# main.net
KiCad netlist of a schematic drawn in EAGLE
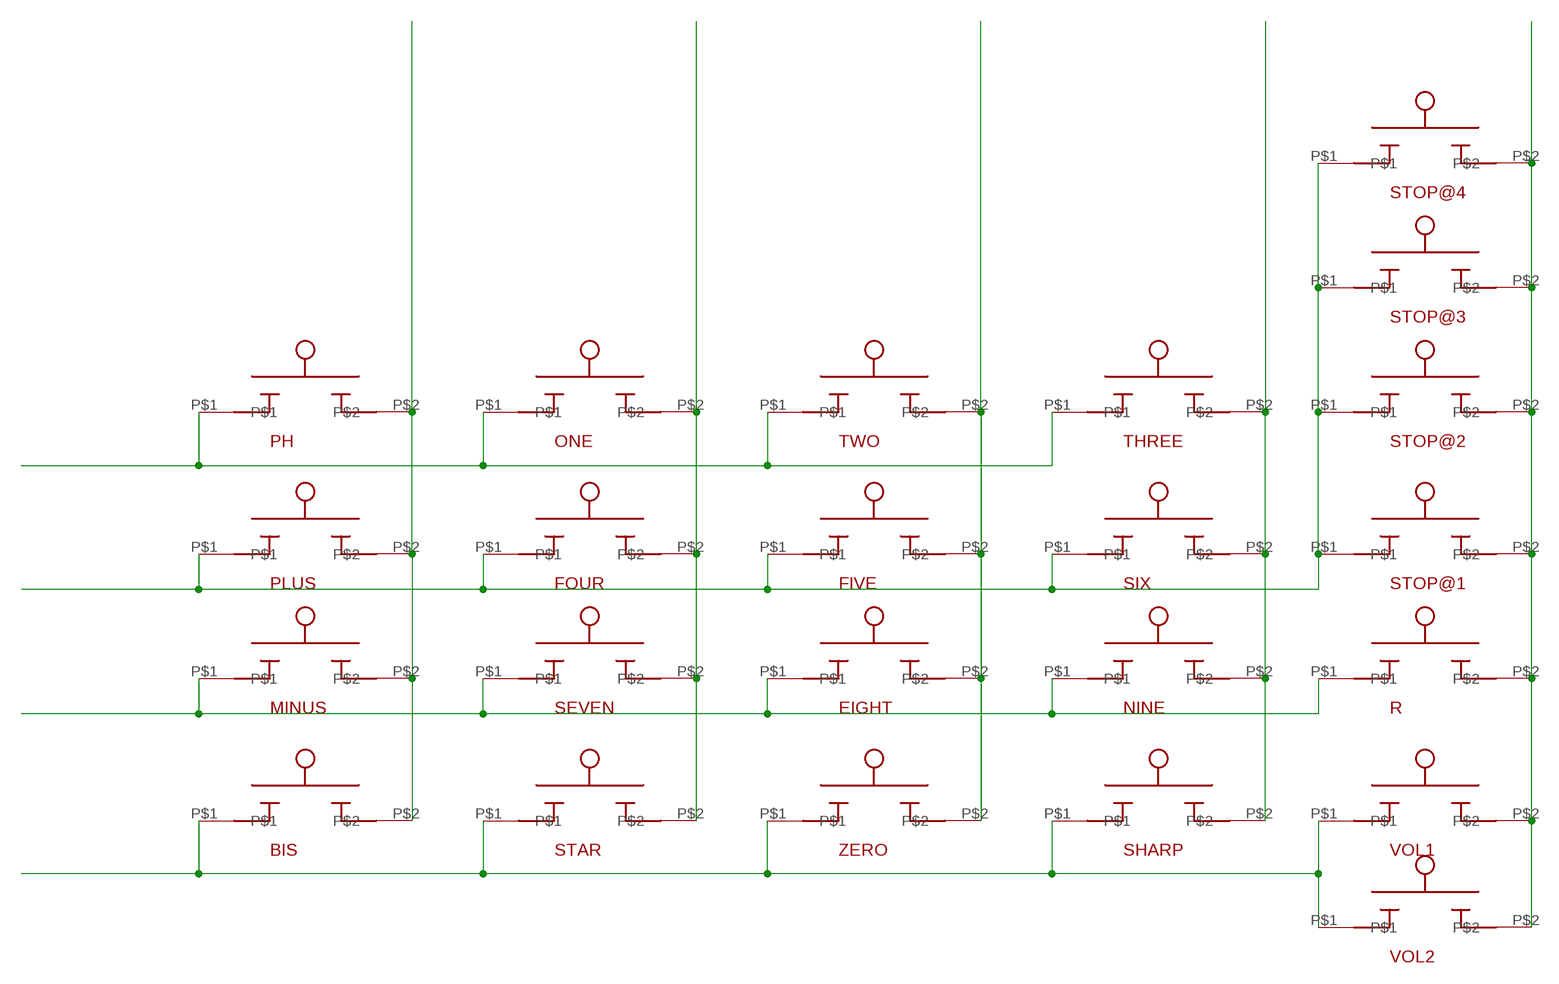
[diagram p0: schematic, sheet 1]

(export (version "E")
  (design (tool "Eeschema 10.0.6"))
  (components
    (comp (ref "BIS")
      (value "MEMBRANE_BUTTON")
      (footprint "eagle-import:MEMBRANE_BUTTON")
      (libsource (lib "eagle-import") (part "7_segment_lib_1964360_MEMBRANE_BUTTON"))
    )
    (comp (ref "EIGHT")
      (value "MEMBRANE_BUTTON")
      (footprint "eagle-import:MEMBRANE_BUTTON")
      (libsource (lib "eagle-import") (part "MEMBRANE_BUTTON"))
    )
    (comp (ref "FIVE")
      (value "MEMBRANE_BUTTON")
      (footprint "eagle-import:MEMBRANE_BUTTON")
      (libsource (lib "eagle-import") (part "MEMBRANE_BUTTON"))
    )
    (comp (ref "FOUR")
      (value "MEMBRANE_BUTTON")
      (footprint "eagle-import:MEMBRANE_BUTTON")
      (libsource (lib "eagle-import") (part "MEMBRANE_BUTTON"))
    )
    (comp (ref "MINUS")
      (value "MEMBRANE_BUTTON")
      (footprint "eagle-import:MEMBRANE_BUTTON")
      (libsource (lib "eagle-import") (part "MEMBRANE_BUTTON"))
    )
    (comp (ref "NINE")
      (value "MEMBRANE_BUTTON")
      (footprint "eagle-import:MEMBRANE_BUTTON")
      (libsource (lib "eagle-import") (part "MEMBRANE_BUTTON"))
    )
    (comp (ref "ONE")
      (value "MEMBRANE_BUTTON")
      (footprint "eagle-import:MEMBRANE_BUTTON")
      (libsource (lib "eagle-import") (part "MEMBRANE_BUTTON"))
    )
    (comp (ref "PH")
      (value "MEMBRANE_BUTTON")
      (footprint "eagle-import:MEMBRANE_BUTTON")
      (libsource (lib "eagle-import") (part "MEMBRANE_BUTTON"))
    )
    (comp (ref "PLUS")
      (value "MEMBRANE_BUTTON")
      (footprint "eagle-import:MEMBRANE_BUTTON")
      (libsource (lib "eagle-import") (part "MEMBRANE_BUTTON"))
    )
    (comp (ref "R")
      (value "MEMBRANE_BUTTON")
      (footprint "eagle-import:MEMBRANE_BUTTON")
      (libsource (lib "eagle-import") (part "MEMBRANE_BUTTON"))
    )
    (comp (ref "SEVEN")
      (value "MEMBRANE_BUTTON")
      (footprint "eagle-import:MEMBRANE_BUTTON")
      (libsource (lib "eagle-import") (part "MEMBRANE_BUTTON"))
    )
    (comp (ref "SHARP")
      (value "MEMBRANE_BUTTON")
      (footprint "eagle-import:MEMBRANE_BUTTON")
      (libsource (lib "eagle-import") (part "MEMBRANE_BUTTON"))
    )
    (comp (ref "SIX")
      (value "MEMBRANE_BUTTON")
      (footprint "eagle-import:MEMBRANE_BUTTON")
      (libsource (lib "eagle-import") (part "MEMBRANE_BUTTON"))
    )
    (comp (ref "STAR")
      (value "MEMBRANE_BUTTON")
      (footprint "eagle-import:MEMBRANE_BUTTON")
      (libsource (lib "eagle-import") (part "MEMBRANE_BUTTON"))
    )
    (comp (ref "STOP@1")
      (value "MEMBRANE_BUTTON")
      (footprint "eagle-import:MEMBRANE_BUTTON")
      (libsource (lib "eagle-import") (part "MEMBRANE_BUTTON"))
    )
    (comp (ref "STOP@2")
      (value "MEMBRANE_BUTTON")
      (footprint "eagle-import:MEMBRANE_BUTTON")
      (libsource (lib "eagle-import") (part "MEMBRANE_BUTTON"))
    )
    (comp (ref "STOP@3")
      (value "MEMBRANE_BUTTON")
      (footprint "eagle-import:MEMBRANE_BUTTON")
      (libsource (lib "eagle-import") (part "MEMBRANE_BUTTON"))
    )
    (comp (ref "STOP@4")
      (value "MEMBRANE_BUTTON")
      (footprint "eagle-import:MEMBRANE_BUTTON")
      (libsource (lib "eagle-import") (part "MEMBRANE_BUTTON"))
    )
    (comp (ref "THREE")
      (value "MEMBRANE_BUTTON")
      (footprint "eagle-import:MEMBRANE_BUTTON")
      (libsource (lib "eagle-import") (part "MEMBRANE_BUTTON"))
    )
    (comp (ref "TWO")
      (value "MEMBRANE_BUTTON")
      (footprint "eagle-import:MEMBRANE_BUTTON")
      (libsource (lib "eagle-import") (part "MEMBRANE_BUTTON"))
    )
    (comp (ref "VOL1")
      (value "MEMBRANE_BUTTON")
      (footprint "eagle-import:MEMBRANE_BUTTON")
      (libsource (lib "eagle-import") (part "MEMBRANE_BUTTON"))
    )
    (comp (ref "VOL2")
      (value "MEMBRANE_BUTTON")
      (footprint "eagle-import:MEMBRANE_BUTTON")
      (libsource (lib "eagle-import") (part "MEMBRANE_BUTTON"))
    )
    (comp (ref "ZERO")
      (value "MEMBRANE_BUTTON")
      (footprint "eagle-import:MEMBRANE_BUTTON")
      (libsource (lib "eagle-import") (part "MEMBRANE_BUTTON"))
    )
  )
  (nets
    (net (code "1") (name "Net-(BIS-PadP$1)") (class "Default")
      (node (ref "BIS") (pin "P$1") (pinfunction "P$1_P$1") (pintype "bidirectional"))
      (node (ref "SHARP") (pin "P$1") (pinfunction "P$1_P$1") (pintype "bidirectional"))
      (node (ref "STAR") (pin "P$1") (pinfunction "P$1_P$1") (pintype "bidirectional"))
      (node (ref "VOL1") (pin "P$1") (pinfunction "P$1_P$1") (pintype "bidirectional"))
      (node (ref "VOL2") (pin "P$1") (pinfunction "P$1_P$1") (pintype "bidirectional"))
      (node (ref "ZERO") (pin "P$1") (pinfunction "P$1_P$1") (pintype "bidirectional"))
    )
    (net (code "2") (name "Net-(BIS-PadP$2)") (class "Default")
      (node (ref "BIS") (pin "P$2") (pinfunction "P$2_P$2") (pintype "bidirectional"))
      (node (ref "MINUS") (pin "P$2") (pinfunction "P$2_P$2") (pintype "bidirectional"))
      (node (ref "PH") (pin "P$2") (pinfunction "P$2_P$2") (pintype "bidirectional"))
      (node (ref "PLUS") (pin "P$2") (pinfunction "P$2_P$2") (pintype "bidirectional"))
    )
    (net (code "3") (name "Net-(EIGHT-PadP$1)") (class "Default")
      (node (ref "EIGHT") (pin "P$1") (pinfunction "P$1_P$1") (pintype "bidirectional"))
      (node (ref "MINUS") (pin "P$1") (pinfunction "P$1_P$1") (pintype "bidirectional"))
      (node (ref "NINE") (pin "P$1") (pinfunction "P$1_P$1") (pintype "bidirectional"))
      (node (ref "R") (pin "P$1") (pinfunction "P$1_P$1") (pintype "bidirectional"))
      (node (ref "SEVEN") (pin "P$1") (pinfunction "P$1_P$1") (pintype "bidirectional"))
    )
    (net (code "4") (name "Net-(EIGHT-PadP$2)") (class "Default")
      (node (ref "EIGHT") (pin "P$2") (pinfunction "P$2_P$2") (pintype "bidirectional"))
      (node (ref "FIVE") (pin "P$2") (pinfunction "P$2_P$2") (pintype "bidirectional"))
      (node (ref "TWO") (pin "P$2") (pinfunction "P$2_P$2") (pintype "bidirectional"))
      (node (ref "ZERO") (pin "P$2") (pinfunction "P$2_P$2") (pintype "bidirectional"))
    )
    (net (code "5") (name "Net-(FIVE-PadP$1)") (class "Default")
      (node (ref "FIVE") (pin "P$1") (pinfunction "P$1_P$1") (pintype "bidirectional"))
      (node (ref "FOUR") (pin "P$1") (pinfunction "P$1_P$1") (pintype "bidirectional"))
      (node (ref "PLUS") (pin "P$1") (pinfunction "P$1_P$1") (pintype "bidirectional"))
      (node (ref "SIX") (pin "P$1") (pinfunction "P$1_P$1") (pintype "bidirectional"))
      (node (ref "STOP@1") (pin "P$1") (pinfunction "P$1_P$1") (pintype "bidirectional"))
      (node (ref "STOP@2") (pin "P$1") (pinfunction "P$1_P$1") (pintype "bidirectional"))
      (node (ref "STOP@3") (pin "P$1") (pinfunction "P$1_P$1") (pintype "bidirectional"))
      (node (ref "STOP@4") (pin "P$1") (pinfunction "P$1_P$1") (pintype "bidirectional"))
    )
    (net (code "6") (name "Net-(FOUR-PadP$2)") (class "Default")
      (node (ref "FOUR") (pin "P$2") (pinfunction "P$2_P$2") (pintype "bidirectional"))
      (node (ref "ONE") (pin "P$2") (pinfunction "P$2_P$2") (pintype "bidirectional"))
      (node (ref "SEVEN") (pin "P$2") (pinfunction "P$2_P$2") (pintype "bidirectional"))
      (node (ref "STAR") (pin "P$2") (pinfunction "P$2_P$2") (pintype "bidirectional"))
    )
    (net (code "7") (name "Net-(NINE-PadP$2)") (class "Default")
      (node (ref "NINE") (pin "P$2") (pinfunction "P$2_P$2") (pintype "bidirectional"))
      (node (ref "SHARP") (pin "P$2") (pinfunction "P$2_P$2") (pintype "bidirectional"))
      (node (ref "SIX") (pin "P$2") (pinfunction "P$2_P$2") (pintype "bidirectional"))
      (node (ref "THREE") (pin "P$2") (pinfunction "P$2_P$2") (pintype "bidirectional"))
    )
    (net (code "8") (name "Net-(ONE-PadP$1)") (class "Default")
      (node (ref "ONE") (pin "P$1") (pinfunction "P$1_P$1") (pintype "bidirectional"))
      (node (ref "PH") (pin "P$1") (pinfunction "P$1_P$1") (pintype "bidirectional"))
      (node (ref "THREE") (pin "P$1") (pinfunction "P$1_P$1") (pintype "bidirectional"))
      (node (ref "TWO") (pin "P$1") (pinfunction "P$1_P$1") (pintype "bidirectional"))
    )
    (net (code "9") (name "Net-(R-PadP$2)") (class "Default")
      (node (ref "R") (pin "P$2") (pinfunction "P$2_P$2") (pintype "bidirectional"))
      (node (ref "STOP@1") (pin "P$2") (pinfunction "P$2_P$2") (pintype "bidirectional"))
      (node (ref "STOP@2") (pin "P$2") (pinfunction "P$2_P$2") (pintype "bidirectional"))
      (node (ref "STOP@3") (pin "P$2") (pinfunction "P$2_P$2") (pintype "bidirectional"))
      (node (ref "STOP@4") (pin "P$2") (pinfunction "P$2_P$2") (pintype "bidirectional"))
      (node (ref "VOL1") (pin "P$2") (pinfunction "P$2_P$2") (pintype "bidirectional"))
      (node (ref "VOL2") (pin "P$2") (pinfunction "P$2_P$2") (pintype "bidirectional"))
    )
  )
)
